# remote_sch.net
KiCad netlist of a schematic drawn in EAGLE
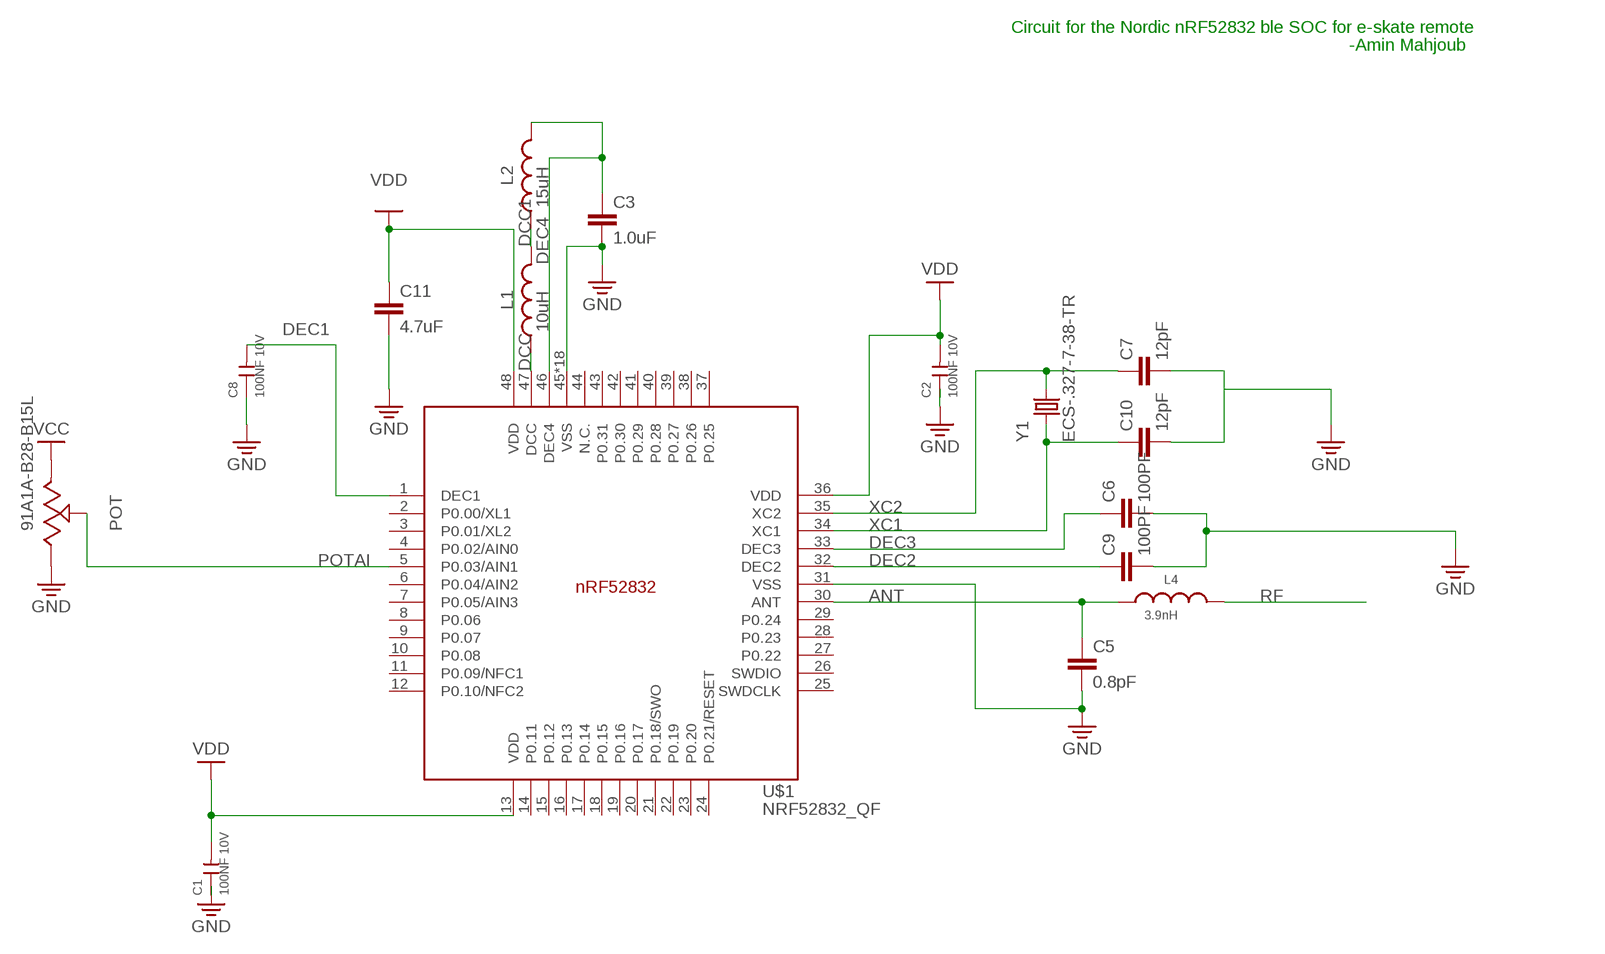
[diagram p0: schematic, sheet 1]

(export (version "E")
  (design (tool "Eeschema 10.0.6"))
  (components
    (comp (ref "C1")
      (value "100NF 10V")
      (footprint "eagle-import:C0402")
      (fields (field (name "MPN") "CC0402KRX5R6BB104"))
      (libsource (lib "eagle-import") (part "CERAMIC 100NF-10V-10%-X5R(0402)"))
    )
    (comp (ref "C2")
      (value "100NF 10V")
      (footprint "eagle-import:C0402")
      (fields (field (name "MPN") "CC0402KRX5R6BB104"))
      (libsource (lib "eagle-import") (part "CERAMIC 100NF-10V-10%-X5R(0402)"))
    )
    (comp (ref "C3")
      (value "1.0uF")
      (footprint "eagle-import:0402")
      (libsource (lib "eagle-import") (part "1.0UF-0402-16V-10%"))
    )
    (comp (ref "C5")
      (value "0.8pF")
      (footprint "eagle-import:0402")
      (libsource (lib "eagle-import") (part "0.8PF-0402-50V-0.1PF"))
    )
    (comp (ref "C6")
      (value "100PF")
      (footprint "eagle-import:0402")
      (libsource (lib "eagle-import") (part "100PF-0402-50V-5%"))
    )
    (comp (ref "C7")
      (value "12pF")
      (footprint "eagle-import:0603")
      (libsource (lib "eagle-import") (part "12PF-0603-50V-5%"))
    )
    (comp (ref "C8")
      (value "100NF 10V")
      (footprint "eagle-import:C0402")
      (fields (field (name "MPN") "CC0402KRX5R6BB104"))
      (libsource (lib "eagle-import") (part "CERAMIC 100NF-10V-10%-X5R(0402)"))
    )
    (comp (ref "C9")
      (value "100PF")
      (footprint "eagle-import:0402")
      (libsource (lib "eagle-import") (part "100PF-0402-50V-5%"))
    )
    (comp (ref "C10")
      (value "12pF")
      (footprint "eagle-import:0603")
      (libsource (lib "eagle-import") (part "12PF-0603-50V-5%"))
    )
    (comp (ref "C11")
      (value "4.7uF")
      (footprint "eagle-import:0402-TIGHT")
      (libsource (lib "eagle-import") (part "4.7UF-0402_TIGHT-6.3V-20%-X5R"))
    )
    (comp (ref "L1")
      (value "10uH")
      (footprint "eagle-import:WE-MAIA_2510")
      (libsource (lib "eagle-import") (part "WE-MAIA_2510_78438323100"))
    )
    (comp (ref "L2")
      (value "15uH")
      (footprint "eagle-import:WE-MAIA_3015")
      (libsource (lib "eagle-import") (part "WE-MAIA_3015_78438335150"))
    )
    (comp (ref "L4")
      (value "3.9nH")
      (footprint "eagle-import:WE-MK_0201")
      (libsource (lib "eagle-import") (part "WE-MK_0201_7447820039"))
    )
    (comp (ref "POT")
      (value "91A1A-B28-B15L")
      (footprint "eagle-import:91A1A-B28-B15L-ND")
      (fields
        (field (name "DIGIKEY_PARTNO") "91A1A-B28-B15L-ND")
        (field (name "MANUFACTURER") "Bourns Inc.")
        (field (name "CREATED_BY") "PCBLayout.com")
      )
      (libsource (lib "eagle-import") (part "91A1A-B28-B15L"))
    )
    (comp (ref "U$1")
      (value "NRF52832_QF")
      (footprint "eagle-import:QFN40P600X600X90-48_N")
      (libsource (lib "eagle-import") (part "NRF52832_QF"))
    )
    (comp (ref "Y1")
      (value "ECS-.327-7-38-TR")
      (footprint "eagle-import:ECS-.327-7-38-TR")
      (fields
        (field (name "DIGIKEY_PART_NUMBER") "XC1657TR-ND")
        (field (name "MANUFACTURER") "ECS Inc.")
        (field (name "CREATED_BY") "PCBLayout.com")
      )
      (libsource (lib "eagle-import") (part "ECS-.327-7-38-TR"))
    )
  )
  (nets
    (net (code "1") (name "/ANT") (class "Default")
      (node (ref "C5") (pin "1") (pinfunction "1_1") (pintype "passive"))
      (node (ref "L4") (pin "1") (pinfunction "1_1") (pintype "passive"))
      (node (ref "U$1") (pin "30") (pinfunction "ANT_30") (pintype "bidirectional"))
    )
    (net (code "2") (name "/DCC") (class "Default")
      (node (ref "L1") (pin "1") (pinfunction "1_1") (pintype "passive"))
      (node (ref "U$1") (pin "47") (pinfunction "DCC_47") (pintype "output"))
    )
    (net (code "3") (name "/DCC1") (class "Default")
      (node (ref "L1") (pin "2") (pinfunction "2_2") (pintype "passive"))
      (node (ref "L2") (pin "1") (pinfunction "1_1") (pintype "passive"))
    )
    (net (code "4") (name "/DEC1") (class "Default")
      (node (ref "C8") (pin "2") (pinfunction "2_2") (pintype "passive"))
      (node (ref "U$1") (pin "1") (pinfunction "DEC1_1") (pintype "power_in"))
    )
    (net (code "5") (name "/DEC2") (class "Default")
      (node (ref "C9") (pin "1") (pinfunction "1_1") (pintype "passive"))
      (node (ref "U$1") (pin "32") (pinfunction "DEC2_32") (pintype "bidirectional"))
    )
    (net (code "6") (name "/DEC3") (class "Default")
      (node (ref "C6") (pin "1") (pinfunction "1_1") (pintype "passive"))
      (node (ref "U$1") (pin "33") (pinfunction "DEC3_33") (pintype "bidirectional"))
    )
    (net (code "7") (name "/DEC4") (class "Default")
      (node (ref "C3") (pin "1") (pinfunction "1_1") (pintype "passive"))
      (node (ref "L2") (pin "2") (pinfunction "2_2") (pintype "passive"))
      (node (ref "U$1") (pin "46") (pinfunction "DEC4_46") (pintype "power_in"))
    )
    (net (code "8") (name "/POTAI") (class "Default")
      (node (ref "POT") (pin "2") (pinfunction "2_2") (pintype "passive"))
      (node (ref "U$1") (pin "5") (pinfunction "P0.03/AIN1_5") (pintype "bidirectional"))
    )
    (net (code "9") (name "/RF") (class "Default")
      (node (ref "L4") (pin "2") (pinfunction "2_2") (pintype "passive"))
    )
    (net (code "10") (name "/XC1") (class "Default")
      (node (ref "C10") (pin "1") (pinfunction "1_1") (pintype "passive"))
      (node (ref "U$1") (pin "34") (pinfunction "XC1_34") (pintype "input"))
      (node (ref "Y1") (pin "1") (pinfunction "1_1") (pintype "passive"))
    )
    (net (code "11") (name "/XC2") (class "Default")
      (node (ref "C7") (pin "1") (pinfunction "1_1") (pintype "passive"))
      (node (ref "U$1") (pin "35") (pinfunction "XC2_35") (pintype "output"))
      (node (ref "Y1") (pin "4") (pinfunction "2_4") (pintype "passive"))
    )
    (net (code "12") (name "GND") (class "Default")
      (node (ref "C1") (pin "1") (pinfunction "1_1") (pintype "passive"))
      (node (ref "C10") (pin "2") (pinfunction "2_2") (pintype "passive"))
      (node (ref "C11") (pin "2") (pinfunction "2_2") (pintype "passive"))
      (node (ref "C2") (pin "1") (pinfunction "1_1") (pintype "passive"))
      (node (ref "C3") (pin "2") (pinfunction "2_2") (pintype "passive"))
      (node (ref "C5") (pin "2") (pinfunction "2_2") (pintype "passive"))
      (node (ref "C6") (pin "2") (pinfunction "2_2") (pintype "passive"))
      (node (ref "C7") (pin "2") (pinfunction "2_2") (pintype "passive"))
      (node (ref "C8") (pin "1") (pinfunction "1_1") (pintype "passive"))
      (node (ref "C9") (pin "2") (pinfunction "2_2") (pintype "passive"))
      (node (ref "POT") (pin "3") (pinfunction "3_3") (pintype "passive"))
      (node (ref "U$1") (pin "31") (pinfunction "VSS_31") (pintype "bidirectional"))
      (node (ref "U$1") (pin "45") (pinfunction "VSS_45") (pintype "power_in"))
      (node (ref "U$1") (pin "PAD") (pinfunction "VSS_PAD") (pintype "power_in"))
      (node (ref "U$1") (pin "PAD@VIA01") (pinfunction "VSS_PAD@VIA01") (pintype "power_in"))
      (node (ref "U$1") (pin "PAD@VIA02") (pinfunction "VSS_PAD@VIA02") (pintype "power_in"))
      (node (ref "U$1") (pin "PAD@VIA03") (pinfunction "VSS_PAD@VIA03") (pintype "power_in"))
      (node (ref "U$1") (pin "PAD@VIA04") (pinfunction "VSS_PAD@VIA04") (pintype "power_in"))
      (node (ref "U$1") (pin "PAD@VIA05") (pinfunction "VSS_PAD@VIA05") (pintype "power_in"))
      (node (ref "U$1") (pin "PAD@VIA06") (pinfunction "VSS_PAD@VIA06") (pintype "power_in"))
      (node (ref "U$1") (pin "PAD@VIA07") (pinfunction "VSS_PAD@VIA07") (pintype "power_in"))
      (node (ref "U$1") (pin "PAD@VIA08") (pinfunction "VSS_PAD@VIA08") (pintype "power_in"))
      (node (ref "U$1") (pin "PAD@VIA09") (pinfunction "VSS_PAD@VIA09") (pintype "power_in"))
      (node (ref "U$1") (pin "PAD@VIA10") (pinfunction "VSS_PAD@VIA10") (pintype "power_in"))
      (node (ref "U$1") (pin "PAD@VIA11") (pinfunction "VSS_PAD@VIA11") (pintype "power_in"))
      (node (ref "U$1") (pin "PAD@VIA12") (pinfunction "VSS_PAD@VIA12") (pintype "power_in"))
      (node (ref "U$1") (pin "PAD@VIA13") (pinfunction "VSS_PAD@VIA13") (pintype "power_in"))
      (node (ref "U$1") (pin "PAD@VIA14") (pinfunction "VSS_PAD@VIA14") (pintype "power_in"))
      (node (ref "U$1") (pin "PAD@VIA15") (pinfunction "VSS_PAD@VIA15") (pintype "power_in"))
      (node (ref "U$1") (pin "PAD@VIA16") (pinfunction "VSS_PAD@VIA16") (pintype "power_in"))
    )
    (net (code "13") (name "VCC") (class "Default")
      (node (ref "POT") (pin "1") (pinfunction "1_1") (pintype "passive"))
    )
    (net (code "14") (name "VDD") (class "Default")
      (node (ref "C1") (pin "2") (pinfunction "2_2") (pintype "passive"))
      (node (ref "C11") (pin "1") (pinfunction "1_1") (pintype "passive"))
      (node (ref "C2") (pin "2") (pinfunction "2_2") (pintype "passive"))
      (node (ref "U$1") (pin "13") (pinfunction "VDD_13") (pintype "power_in"))
      (node (ref "U$1") (pin "36") (pinfunction "VDD_36") (pintype "power_in"))
      (node (ref "U$1") (pin "48") (pinfunction "VDD_48") (pintype "power_in"))
    )
    (net (code "15") (name "unconnected-(U$1-N.C.-Pad44)") (class "Default")
      (node (ref "U$1") (pin "44") (pinfunction "N.C._44") (pintype "no_connect"))
    )
    (net (code "16") (name "unconnected-(U$1-P0.00{slash}XL1-Pad2)") (class "Default")
      (node (ref "U$1") (pin "2") (pinfunction "P0.00/XL1_2") (pintype "bidirectional"))
    )
    (net (code "17") (name "unconnected-(U$1-P0.01{slash}XL2-Pad3)") (class "Default")
      (node (ref "U$1") (pin "3") (pinfunction "P0.01/XL2_3") (pintype "bidirectional"))
    )
    (net (code "18") (name "unconnected-(U$1-P0.02{slash}AIN0-Pad4)") (class "Default")
      (node (ref "U$1") (pin "4") (pinfunction "P0.02/AIN0_4") (pintype "bidirectional"))
    )
    (net (code "19") (name "unconnected-(U$1-P0.04{slash}AIN2-Pad6)") (class "Default")
      (node (ref "U$1") (pin "6") (pinfunction "P0.04/AIN2_6") (pintype "bidirectional"))
    )
    (net (code "20") (name "unconnected-(U$1-P0.05{slash}AIN3-Pad7)") (class "Default")
      (node (ref "U$1") (pin "7") (pinfunction "P0.05/AIN3_7") (pintype "bidirectional"))
    )
    (net (code "21") (name "unconnected-(U$1-P0.06-Pad8)") (class "Default")
      (node (ref "U$1") (pin "8") (pinfunction "P0.06_8") (pintype "bidirectional"))
    )
    (net (code "22") (name "unconnected-(U$1-P0.07-Pad9)") (class "Default")
      (node (ref "U$1") (pin "9") (pinfunction "P0.07_9") (pintype "bidirectional"))
    )
    (net (code "23") (name "unconnected-(U$1-P0.08-Pad10)") (class "Default")
      (node (ref "U$1") (pin "10") (pinfunction "P0.08_10") (pintype "bidirectional"))
    )
    (net (code "24") (name "unconnected-(U$1-P0.09{slash}NFC1-Pad11)") (class "Default")
      (node (ref "U$1") (pin "11") (pinfunction "P0.09/NFC1_11") (pintype "bidirectional"))
    )
    (net (code "25") (name "unconnected-(U$1-P0.10{slash}NFC2-Pad12)") (class "Default")
      (node (ref "U$1") (pin "12") (pinfunction "P0.10/NFC2_12") (pintype "bidirectional"))
    )
    (net (code "26") (name "unconnected-(U$1-P0.11-Pad14)") (class "Default")
      (node (ref "U$1") (pin "14") (pinfunction "P0.11_14") (pintype "bidirectional"))
    )
    (net (code "27") (name "unconnected-(U$1-P0.12-Pad15)") (class "Default")
      (node (ref "U$1") (pin "15") (pinfunction "P0.12_15") (pintype "bidirectional"))
    )
    (net (code "28") (name "unconnected-(U$1-P0.13-Pad16)") (class "Default")
      (node (ref "U$1") (pin "16") (pinfunction "P0.13_16") (pintype "bidirectional"))
    )
    (net (code "29") (name "unconnected-(U$1-P0.14-Pad17)") (class "Default")
      (node (ref "U$1") (pin "17") (pinfunction "P0.14_17") (pintype "bidirectional"))
    )
    (net (code "30") (name "unconnected-(U$1-P0.15-Pad18)") (class "Default")
      (node (ref "U$1") (pin "18") (pinfunction "P0.15_18") (pintype "bidirectional"))
    )
    (net (code "31") (name "unconnected-(U$1-P0.16-Pad19)") (class "Default")
      (node (ref "U$1") (pin "19") (pinfunction "P0.16_19") (pintype "bidirectional"))
    )
    (net (code "32") (name "unconnected-(U$1-P0.17-Pad20)") (class "Default")
      (node (ref "U$1") (pin "20") (pinfunction "P0.17_20") (pintype "bidirectional"))
    )
    (net (code "33") (name "unconnected-(U$1-P0.18{slash}SWO-Pad21)") (class "Default")
      (node (ref "U$1") (pin "21") (pinfunction "P0.18/SWO_21") (pintype "bidirectional"))
    )
    (net (code "34") (name "unconnected-(U$1-P0.19-Pad22)") (class "Default")
      (node (ref "U$1") (pin "22") (pinfunction "P0.19_22") (pintype "bidirectional"))
    )
    (net (code "35") (name "unconnected-(U$1-P0.20-Pad23)") (class "Default")
      (node (ref "U$1") (pin "23") (pinfunction "P0.20_23") (pintype "bidirectional"))
    )
    (net (code "36") (name "unconnected-(U$1-P0.21{slash}RESET-Pad24)") (class "Default")
      (node (ref "U$1") (pin "24") (pinfunction "P0.21/RESET_24") (pintype "bidirectional"))
    )
    (net (code "37") (name "unconnected-(U$1-P0.22-Pad27)") (class "Default")
      (node (ref "U$1") (pin "27") (pinfunction "P0.22_27") (pintype "bidirectional"))
    )
    (net (code "38") (name "unconnected-(U$1-P0.23-Pad28)") (class "Default")
      (node (ref "U$1") (pin "28") (pinfunction "P0.23_28") (pintype "bidirectional"))
    )
    (net (code "39") (name "unconnected-(U$1-P0.24-Pad29)") (class "Default")
      (node (ref "U$1") (pin "29") (pinfunction "P0.24_29") (pintype "bidirectional"))
    )
    (net (code "40") (name "unconnected-(U$1-P0.25-Pad37)") (class "Default")
      (node (ref "U$1") (pin "37") (pinfunction "P0.25_37") (pintype "bidirectional"))
    )
    (net (code "41") (name "unconnected-(U$1-P0.26-Pad38)") (class "Default")
      (node (ref "U$1") (pin "38") (pinfunction "P0.26_38") (pintype "bidirectional"))
    )
    (net (code "42") (name "unconnected-(U$1-P0.27-Pad39)") (class "Default")
      (node (ref "U$1") (pin "39") (pinfunction "P0.27_39") (pintype "bidirectional"))
    )
    (net (code "43") (name "unconnected-(U$1-P0.28-Pad40)") (class "Default")
      (node (ref "U$1") (pin "40") (pinfunction "P0.28_40") (pintype "bidirectional"))
    )
    (net (code "44") (name "unconnected-(U$1-P0.29-Pad41)") (class "Default")
      (node (ref "U$1") (pin "41") (pinfunction "P0.29_41") (pintype "bidirectional"))
    )
    (net (code "45") (name "unconnected-(U$1-P0.30-Pad42)") (class "Default")
      (node (ref "U$1") (pin "42") (pinfunction "P0.30_42") (pintype "bidirectional"))
    )
    (net (code "46") (name "unconnected-(U$1-P0.31-Pad43)") (class "Default")
      (node (ref "U$1") (pin "43") (pinfunction "P0.31_43") (pintype "bidirectional"))
    )
    (net (code "47") (name "unconnected-(U$1-SWDCLK-Pad25)") (class "Default")
      (node (ref "U$1") (pin "25") (pinfunction "SWDCLK_25") (pintype "input"))
    )
    (net (code "48") (name "unconnected-(U$1-SWDIO-Pad26)") (class "Default")
      (node (ref "U$1") (pin "26") (pinfunction "SWDIO_26") (pintype "bidirectional"))
    )
  )
)
